# exp20.net
KiCad netlist of a schematic drawn in EAGLE
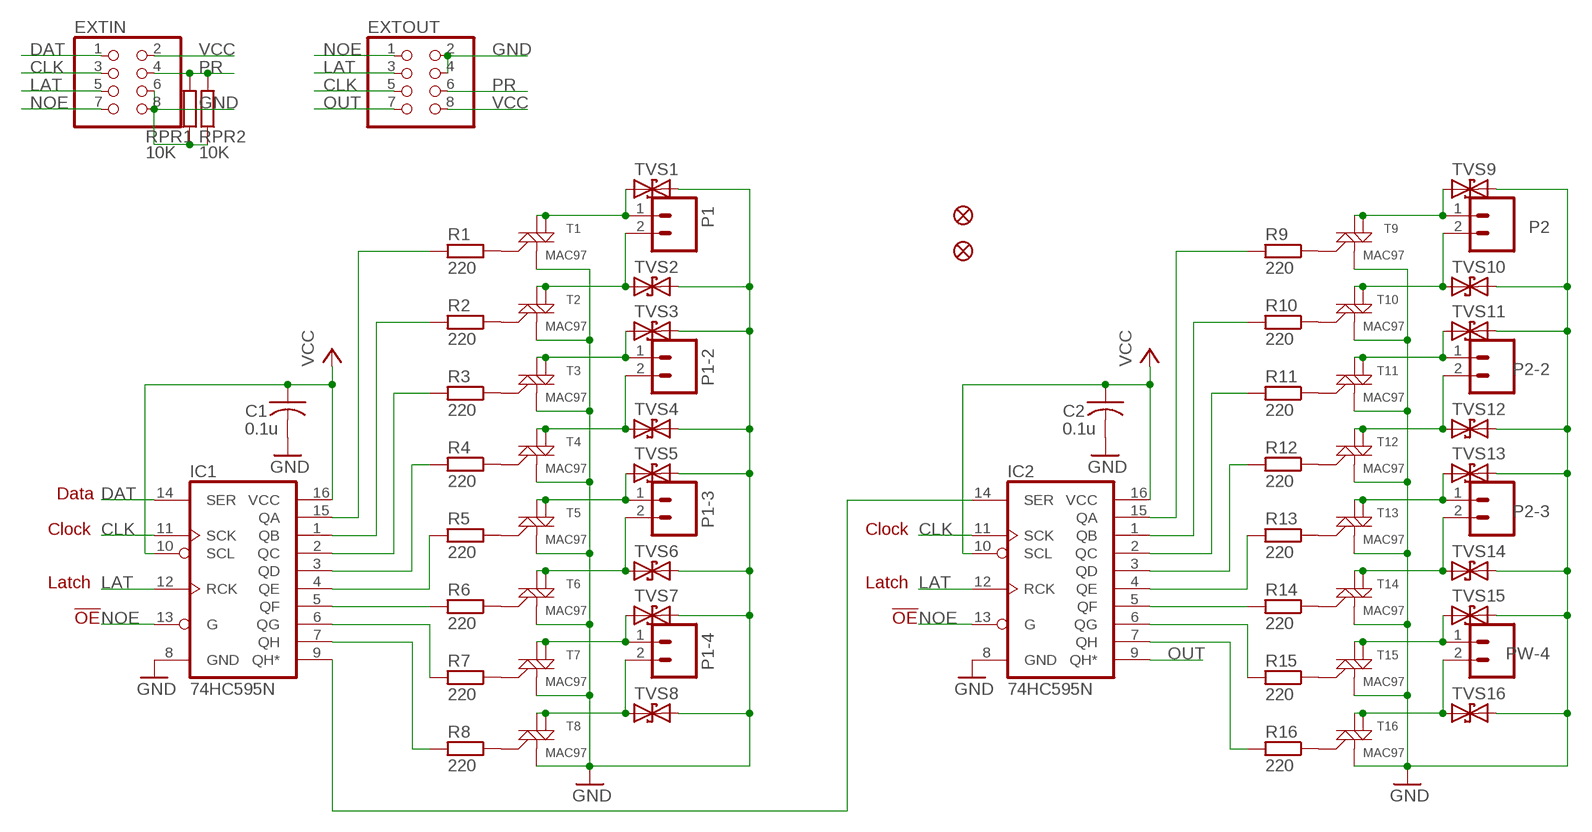
[diagram p0: schematic, sheet 1]

(export (version "E")
  (design (tool "Eeschema 10.0.6"))
  (components
    (comp (ref "C1")
      (value "0.1u")
      (footprint "eagle-import:C0805K")
      (libsource (lib "eagle-import") (part "C-USC0805K"))
    )
    (comp (ref "C2")
      (value "0.1u")
      (footprint "eagle-import:C0805K")
      (libsource (lib "eagle-import") (part "C-USC0805K"))
    )
    (comp (ref "EXTIN")
      (value "PINHD-2X4/90")
      (footprint "eagle-import:2X04_90")
      (libsource (lib "eagle-import") (part "PINHD-2X4/90"))
    )
    (comp (ref "EXTOUT")
      (value "PINHD-2X4/90")
      (footprint "eagle-import:2X04_90")
      (libsource (lib "eagle-import") (part "PINHD-2X4/90"))
    )
    (comp (ref "IC1")
      (value "74HC595N")
      (footprint "eagle-import:SO16")
      (libsource (lib "eagle-import") (part "74595DLS"))
    )
    (comp (ref "IC2")
      (value "74HC595N")
      (footprint "eagle-import:SO16")
      (libsource (lib "eagle-import") (part "74595DLS"))
    )
    (comp (ref "JP1")
      (value "FIDUCIAL1X2")
      (footprint "eagle-import:FIDUCIAL-1X2")
      (libsource (lib "eagle-import") (part "FIDUCIAL1X2"))
    )
    (comp (ref "JP2")
      (value "FIDUCIAL1X2")
      (footprint "eagle-import:FIDUCIAL-1X2")
      (libsource (lib "eagle-import") (part "FIDUCIAL1X2"))
    )
    (comp (ref "P1")
      (value "M025MM-X")
      (footprint "eagle-import:SCREWTERMINAL-5MM-2-X")
      (libsource (lib "eagle-import") (part "M025MM-X"))
    )
    (comp (ref "P1-2")
      (value "M025MM-X")
      (footprint "eagle-import:SCREWTERMINAL-5MM-2-X")
      (libsource (lib "eagle-import") (part "M025MM-X"))
    )
    (comp (ref "P1-3")
      (value "M025MM-X")
      (footprint "eagle-import:SCREWTERMINAL-5MM-2-X")
      (libsource (lib "eagle-import") (part "M025MM-X"))
    )
    (comp (ref "P1-4")
      (value "M025MM-X")
      (footprint "eagle-import:SCREWTERMINAL-5MM-2-X")
      (libsource (lib "eagle-import") (part "M025MM-X"))
    )
    (comp (ref "P2")
      (value "M025MM-X")
      (footprint "eagle-import:SCREWTERMINAL-5MM-2-X")
      (libsource (lib "eagle-import") (part "M025MM-X"))
    )
    (comp (ref "P2-2")
      (value "M025MM-X")
      (footprint "eagle-import:SCREWTERMINAL-5MM-2-X")
      (libsource (lib "eagle-import") (part "M025MM-X"))
    )
    (comp (ref "P2-3")
      (value "M025MM-X")
      (footprint "eagle-import:SCREWTERMINAL-5MM-2-X")
      (libsource (lib "eagle-import") (part "M025MM-X"))
    )
    (comp (ref "PW-4")
      (value "M025MM-X")
      (footprint "eagle-import:SCREWTERMINAL-5MM-2-X")
      (libsource (lib "eagle-import") (part "M025MM-X"))
    )
    (comp (ref "R1")
      (value "220")
      (footprint "eagle-import:R0805")
      (libsource (lib "eagle-import") (part "R-EU_R0805"))
    )
    (comp (ref "R2")
      (value "220")
      (footprint "eagle-import:R0805")
      (libsource (lib "eagle-import") (part "R-EU_R0805"))
    )
    (comp (ref "R3")
      (value "220")
      (footprint "eagle-import:R0805")
      (libsource (lib "eagle-import") (part "R-EU_R0805"))
    )
    (comp (ref "R4")
      (value "220")
      (footprint "eagle-import:R0805")
      (libsource (lib "eagle-import") (part "R-EU_R0805"))
    )
    (comp (ref "R5")
      (value "220")
      (footprint "eagle-import:R0805")
      (libsource (lib "eagle-import") (part "R-EU_R0805"))
    )
    (comp (ref "R6")
      (value "220")
      (footprint "eagle-import:R0805")
      (libsource (lib "eagle-import") (part "R-EU_R0805"))
    )
    (comp (ref "R7")
      (value "220")
      (footprint "eagle-import:R0805")
      (libsource (lib "eagle-import") (part "R-EU_R0805"))
    )
    (comp (ref "R8")
      (value "220")
      (footprint "eagle-import:R0805")
      (libsource (lib "eagle-import") (part "R-EU_R0805"))
    )
    (comp (ref "R9")
      (value "220")
      (footprint "eagle-import:R0805")
      (libsource (lib "eagle-import") (part "R-EU_R0805"))
    )
    (comp (ref "R10")
      (value "220")
      (footprint "eagle-import:R0805")
      (libsource (lib "eagle-import") (part "R-EU_R0805"))
    )
    (comp (ref "R11")
      (value "220")
      (footprint "eagle-import:R0805")
      (libsource (lib "eagle-import") (part "R-EU_R0805"))
    )
    (comp (ref "R12")
      (value "220")
      (footprint "eagle-import:R0805")
      (libsource (lib "eagle-import") (part "R-EU_R0805"))
    )
    (comp (ref "R13")
      (value "220")
      (footprint "eagle-import:R0805")
      (libsource (lib "eagle-import") (part "R-EU_R0805"))
    )
    (comp (ref "R14")
      (value "220")
      (footprint "eagle-import:R0805")
      (libsource (lib "eagle-import") (part "R-EU_R0805"))
    )
    (comp (ref "R15")
      (value "220")
      (footprint "eagle-import:R0805")
      (libsource (lib "eagle-import") (part "R-EU_R0805"))
    )
    (comp (ref "R16")
      (value "220")
      (footprint "eagle-import:R0805")
      (libsource (lib "eagle-import") (part "R-EU_R0805"))
    )
    (comp (ref "RPR1")
      (value "10K")
      (footprint "eagle-import:R0805")
      (libsource (lib "eagle-import") (part "R-EU_R0805"))
    )
    (comp (ref "RPR2")
      (value "10K")
      (footprint "eagle-import:R0805")
      (libsource (lib "eagle-import") (part "R-EU_R0805"))
    )
    (comp (ref "T1")
      (value "MAC97")
      (footprint "eagle-import:SOT223")
      (libsource (lib "eagle-import") (part "MAC97SOT223"))
    )
    (comp (ref "T2")
      (value "MAC97")
      (footprint "eagle-import:SOT223")
      (libsource (lib "eagle-import") (part "MAC97SOT223"))
    )
    (comp (ref "T3")
      (value "MAC97")
      (footprint "eagle-import:SOT223")
      (libsource (lib "eagle-import") (part "MAC97SOT223"))
    )
    (comp (ref "T4")
      (value "MAC97")
      (footprint "eagle-import:SOT223")
      (libsource (lib "eagle-import") (part "MAC97SOT223"))
    )
    (comp (ref "T5")
      (value "MAC97")
      (footprint "eagle-import:SOT223")
      (libsource (lib "eagle-import") (part "MAC97SOT223"))
    )
    (comp (ref "T6")
      (value "MAC97")
      (footprint "eagle-import:SOT223")
      (libsource (lib "eagle-import") (part "MAC97SOT223"))
    )
    (comp (ref "T7")
      (value "MAC97")
      (footprint "eagle-import:SOT223")
      (libsource (lib "eagle-import") (part "MAC97SOT223"))
    )
    (comp (ref "T8")
      (value "MAC97")
      (footprint "eagle-import:SOT223")
      (libsource (lib "eagle-import") (part "MAC97SOT223"))
    )
    (comp (ref "T9")
      (value "MAC97")
      (footprint "eagle-import:SOT223")
      (libsource (lib "eagle-import") (part "MAC97SOT223"))
    )
    (comp (ref "T10")
      (value "MAC97")
      (footprint "eagle-import:SOT223")
      (libsource (lib "eagle-import") (part "MAC97SOT223"))
    )
    (comp (ref "T11")
      (value "MAC97")
      (footprint "eagle-import:SOT223")
      (libsource (lib "eagle-import") (part "MAC97SOT223"))
    )
    (comp (ref "T12")
      (value "MAC97")
      (footprint "eagle-import:SOT223")
      (libsource (lib "eagle-import") (part "MAC97SOT223"))
    )
    (comp (ref "T13")
      (value "MAC97")
      (footprint "eagle-import:SOT223")
      (libsource (lib "eagle-import") (part "MAC97SOT223"))
    )
    (comp (ref "T14")
      (value "MAC97")
      (footprint "eagle-import:SOT223")
      (libsource (lib "eagle-import") (part "MAC97SOT223"))
    )
    (comp (ref "T15")
      (value "MAC97")
      (footprint "eagle-import:SOT223")
      (libsource (lib "eagle-import") (part "MAC97SOT223"))
    )
    (comp (ref "T16")
      (value "MAC97")
      (footprint "eagle-import:SOT223")
      (libsource (lib "eagle-import") (part "MAC97SOT223"))
    )
    (comp (ref "TVS1")
      (value "TVSSMB")
      (footprint "eagle-import:SMB")
      (libsource (lib "eagle-import") (part "TVSSMB"))
    )
    (comp (ref "TVS2")
      (value "TVSSMB")
      (footprint "eagle-import:SMB")
      (libsource (lib "eagle-import") (part "TVSSMB"))
    )
    (comp (ref "TVS3")
      (value "TVSSMB")
      (footprint "eagle-import:SMB")
      (libsource (lib "eagle-import") (part "TVSSMB"))
    )
    (comp (ref "TVS4")
      (value "TVSSMB")
      (footprint "eagle-import:SMB")
      (libsource (lib "eagle-import") (part "TVSSMB"))
    )
    (comp (ref "TVS5")
      (value "TVSSMB")
      (footprint "eagle-import:SMB")
      (libsource (lib "eagle-import") (part "TVSSMB"))
    )
    (comp (ref "TVS6")
      (value "TVSSMB")
      (footprint "eagle-import:SMB")
      (libsource (lib "eagle-import") (part "TVSSMB"))
    )
    (comp (ref "TVS7")
      (value "TVSSMB")
      (footprint "eagle-import:SMB")
      (libsource (lib "eagle-import") (part "TVSSMB"))
    )
    (comp (ref "TVS8")
      (value "TVSSMB")
      (footprint "eagle-import:SMB")
      (libsource (lib "eagle-import") (part "TVSSMB"))
    )
    (comp (ref "TVS9")
      (value "TVSSMB")
      (footprint "eagle-import:SMB")
      (libsource (lib "eagle-import") (part "TVSSMB"))
    )
    (comp (ref "TVS10")
      (value "TVSSMB")
      (footprint "eagle-import:SMB")
      (libsource (lib "eagle-import") (part "TVSSMB"))
    )
    (comp (ref "TVS11")
      (value "TVSSMB")
      (footprint "eagle-import:SMB")
      (libsource (lib "eagle-import") (part "TVSSMB"))
    )
    (comp (ref "TVS12")
      (value "TVSSMB")
      (footprint "eagle-import:SMB")
      (libsource (lib "eagle-import") (part "TVSSMB"))
    )
    (comp (ref "TVS13")
      (value "TVSSMB")
      (footprint "eagle-import:SMB")
      (libsource (lib "eagle-import") (part "TVSSMB"))
    )
    (comp (ref "TVS14")
      (value "TVSSMB")
      (footprint "eagle-import:SMB")
      (libsource (lib "eagle-import") (part "TVSSMB"))
    )
    (comp (ref "TVS15")
      (value "TVSSMB")
      (footprint "eagle-import:SMB")
      (libsource (lib "eagle-import") (part "TVSSMB"))
    )
    (comp (ref "TVS16")
      (value "TVSSMB")
      (footprint "eagle-import:SMB")
      (libsource (lib "eagle-import") (part "TVSSMB"))
    )
  )
  (nets
    (net (code "1") (name "/CLK") (class "Default")
      (node (ref "EXTIN") (pin "3") (pinfunction "3_3") (pintype "passive"))
      (node (ref "EXTOUT") (pin "5") (pinfunction "5_5") (pintype "passive"))
      (node (ref "IC1") (pin "11") (pinfunction "SCK_11") (pintype "input"))
      (node (ref "IC2") (pin "11") (pinfunction "SCK_11") (pintype "input"))
    )
    (net (code "2") (name "/DAT") (class "Default")
      (node (ref "EXTIN") (pin "1") (pinfunction "1_1") (pintype "passive"))
      (node (ref "IC1") (pin "14") (pinfunction "SER_14") (pintype "input"))
    )
    (net (code "3") (name "/LAT") (class "Default")
      (node (ref "EXTIN") (pin "5") (pinfunction "5_5") (pintype "passive"))
      (node (ref "EXTOUT") (pin "3") (pinfunction "3_3") (pintype "passive"))
      (node (ref "IC1") (pin "12") (pinfunction "RCK_12") (pintype "input"))
      (node (ref "IC2") (pin "12") (pinfunction "RCK_12") (pintype "input"))
    )
    (net (code "4") (name "/NOE") (class "Default")
      (node (ref "EXTIN") (pin "7") (pinfunction "7_7") (pintype "passive"))
      (node (ref "EXTOUT") (pin "1") (pinfunction "1_1") (pintype "passive"))
      (node (ref "IC1") (pin "13") (pinfunction "G_13") (pintype "input"))
      (node (ref "IC2") (pin "13") (pinfunction "G_13") (pintype "input"))
    )
    (net (code "5") (name "/OUT") (class "Default")
      (node (ref "EXTOUT") (pin "7") (pinfunction "7_7") (pintype "passive"))
      (node (ref "IC2") (pin "9") (pinfunction "QH*_9") (pintype "tri_state"))
    )
    (net (code "6") (name "/PR") (class "Default")
      (node (ref "EXTIN") (pin "4") (pinfunction "4_4") (pintype "passive"))
      (node (ref "EXTOUT") (pin "6") (pinfunction "6_6") (pintype "passive"))
      (node (ref "RPR1") (pin "2") (pinfunction "2_2") (pintype "passive"))
      (node (ref "RPR2") (pin "2") (pinfunction "2_2") (pintype "passive"))
    )
    (net (code "7") (name "GND") (class "Default")
      (node (ref "C1") (pin "2") (pinfunction "2_2") (pintype "passive"))
      (node (ref "C2") (pin "2") (pinfunction "2_2") (pintype "passive"))
      (node (ref "EXTIN") (pin "6") (pinfunction "6_6") (pintype "passive"))
      (node (ref "EXTIN") (pin "8") (pinfunction "8_8") (pintype "passive"))
      (node (ref "EXTOUT") (pin "2") (pinfunction "2_2") (pintype "passive"))
      (node (ref "EXTOUT") (pin "4") (pinfunction "4_4") (pintype "passive"))
      (node (ref "IC1") (pin "8") (pinfunction "GND_8") (pintype "power_in"))
      (node (ref "IC2") (pin "8") (pinfunction "GND_8") (pintype "power_in"))
      (node (ref "RPR1") (pin "1") (pinfunction "1_1") (pintype "passive"))
      (node (ref "RPR2") (pin "1") (pinfunction "1_1") (pintype "passive"))
      (node (ref "T1") (pin "1") (pinfunction "M1_1") (pintype "bidirectional"))
      (node (ref "T10") (pin "1") (pinfunction "M1_1") (pintype "bidirectional"))
      (node (ref "T11") (pin "1") (pinfunction "M1_1") (pintype "bidirectional"))
      (node (ref "T12") (pin "1") (pinfunction "M1_1") (pintype "bidirectional"))
      (node (ref "T13") (pin "1") (pinfunction "M1_1") (pintype "bidirectional"))
      (node (ref "T14") (pin "1") (pinfunction "M1_1") (pintype "bidirectional"))
      (node (ref "T15") (pin "1") (pinfunction "M1_1") (pintype "bidirectional"))
      (node (ref "T16") (pin "1") (pinfunction "M1_1") (pintype "bidirectional"))
      (node (ref "T2") (pin "1") (pinfunction "M1_1") (pintype "bidirectional"))
      (node (ref "T3") (pin "1") (pinfunction "M1_1") (pintype "bidirectional"))
      (node (ref "T4") (pin "1") (pinfunction "M1_1") (pintype "bidirectional"))
      (node (ref "T5") (pin "1") (pinfunction "M1_1") (pintype "bidirectional"))
      (node (ref "T6") (pin "1") (pinfunction "M1_1") (pintype "bidirectional"))
      (node (ref "T7") (pin "1") (pinfunction "M1_1") (pintype "bidirectional"))
      (node (ref "T8") (pin "1") (pinfunction "M1_1") (pintype "bidirectional"))
      (node (ref "T9") (pin "1") (pinfunction "M1_1") (pintype "bidirectional"))
      (node (ref "TVS1") (pin "C") (pinfunction "2_C") (pintype "passive"))
      (node (ref "TVS10") (pin "C") (pinfunction "2_C") (pintype "passive"))
      (node (ref "TVS11") (pin "C") (pinfunction "2_C") (pintype "passive"))
      (node (ref "TVS12") (pin "C") (pinfunction "2_C") (pintype "passive"))
      (node (ref "TVS13") (pin "C") (pinfunction "2_C") (pintype "passive"))
      (node (ref "TVS14") (pin "C") (pinfunction "2_C") (pintype "passive"))
      (node (ref "TVS15") (pin "C") (pinfunction "2_C") (pintype "passive"))
      (node (ref "TVS16") (pin "C") (pinfunction "2_C") (pintype "passive"))
      (node (ref "TVS2") (pin "C") (pinfunction "2_C") (pintype "passive"))
      (node (ref "TVS3") (pin "C") (pinfunction "2_C") (pintype "passive"))
      (node (ref "TVS4") (pin "C") (pinfunction "2_C") (pintype "passive"))
      (node (ref "TVS5") (pin "C") (pinfunction "2_C") (pintype "passive"))
      (node (ref "TVS6") (pin "C") (pinfunction "2_C") (pintype "passive"))
      (node (ref "TVS7") (pin "C") (pinfunction "2_C") (pintype "passive"))
      (node (ref "TVS8") (pin "C") (pinfunction "2_C") (pintype "passive"))
      (node (ref "TVS9") (pin "C") (pinfunction "2_C") (pintype "passive"))
    )
    (net (code "8") (name "Net-(IC1-QA)") (class "Default")
      (node (ref "IC1") (pin "15") (pinfunction "QA_15") (pintype "tri_state"))
      (node (ref "R1") (pin "2") (pinfunction "2_2") (pintype "passive"))
    )
    (net (code "9") (name "Net-(IC1-QB)") (class "Default")
      (node (ref "IC1") (pin "1") (pinfunction "QB_1") (pintype "tri_state"))
      (node (ref "R2") (pin "2") (pinfunction "2_2") (pintype "passive"))
    )
    (net (code "10") (name "Net-(IC1-QC)") (class "Default")
      (node (ref "IC1") (pin "2") (pinfunction "QC_2") (pintype "tri_state"))
      (node (ref "R3") (pin "2") (pinfunction "2_2") (pintype "passive"))
    )
    (net (code "11") (name "Net-(IC1-QD)") (class "Default")
      (node (ref "IC1") (pin "3") (pinfunction "QD_3") (pintype "tri_state"))
      (node (ref "R4") (pin "2") (pinfunction "2_2") (pintype "passive"))
    )
    (net (code "12") (name "Net-(IC1-QE)") (class "Default")
      (node (ref "IC1") (pin "4") (pinfunction "QE_4") (pintype "tri_state"))
      (node (ref "R5") (pin "2") (pinfunction "2_2") (pintype "passive"))
    )
    (net (code "13") (name "Net-(IC1-QF)") (class "Default")
      (node (ref "IC1") (pin "5") (pinfunction "QF_5") (pintype "tri_state"))
      (node (ref "R6") (pin "2") (pinfunction "2_2") (pintype "passive"))
    )
    (net (code "14") (name "Net-(IC1-QG)") (class "Default")
      (node (ref "IC1") (pin "6") (pinfunction "QG_6") (pintype "tri_state"))
      (node (ref "R7") (pin "2") (pinfunction "2_2") (pintype "passive"))
    )
    (net (code "15") (name "Net-(IC1-QH)") (class "Default")
      (node (ref "IC1") (pin "7") (pinfunction "QH_7") (pintype "tri_state"))
      (node (ref "R8") (pin "2") (pinfunction "2_2") (pintype "passive"))
    )
    (net (code "16") (name "Net-(IC1-QH*)") (class "Default")
      (node (ref "IC1") (pin "9") (pinfunction "QH*_9") (pintype "tri_state"))
      (node (ref "IC2") (pin "14") (pinfunction "SER_14") (pintype "input"))
    )
    (net (code "17") (name "Net-(IC2-QA)") (class "Default")
      (node (ref "IC2") (pin "15") (pinfunction "QA_15") (pintype "tri_state"))
      (node (ref "R9") (pin "2") (pinfunction "2_2") (pintype "passive"))
    )
    (net (code "18") (name "Net-(IC2-QB)") (class "Default")
      (node (ref "IC2") (pin "1") (pinfunction "QB_1") (pintype "tri_state"))
      (node (ref "R10") (pin "2") (pinfunction "2_2") (pintype "passive"))
    )
    (net (code "19") (name "Net-(IC2-QC)") (class "Default")
      (node (ref "IC2") (pin "2") (pinfunction "QC_2") (pintype "tri_state"))
      (node (ref "R11") (pin "2") (pinfunction "2_2") (pintype "passive"))
    )
    (net (code "20") (name "Net-(IC2-QD)") (class "Default")
      (node (ref "IC2") (pin "3") (pinfunction "QD_3") (pintype "tri_state"))
      (node (ref "R12") (pin "2") (pinfunction "2_2") (pintype "passive"))
    )
    (net (code "21") (name "Net-(IC2-QE)") (class "Default")
      (node (ref "IC2") (pin "4") (pinfunction "QE_4") (pintype "tri_state"))
      (node (ref "R13") (pin "2") (pinfunction "2_2") (pintype "passive"))
    )
    (net (code "22") (name "Net-(IC2-QF)") (class "Default")
      (node (ref "IC2") (pin "5") (pinfunction "QF_5") (pintype "tri_state"))
      (node (ref "R14") (pin "2") (pinfunction "2_2") (pintype "passive"))
    )
    (net (code "23") (name "Net-(IC2-QG)") (class "Default")
      (node (ref "IC2") (pin "6") (pinfunction "QG_6") (pintype "tri_state"))
      (node (ref "R15") (pin "2") (pinfunction "2_2") (pintype "passive"))
    )
    (net (code "24") (name "Net-(IC2-QH)") (class "Default")
      (node (ref "IC2") (pin "7") (pinfunction "QH_7") (pintype "tri_state"))
      (node (ref "R16") (pin "2") (pinfunction "2_2") (pintype "passive"))
    )
    (net (code "25") (name "Net-(T1-G)") (class "Default")
      (node (ref "R1") (pin "1") (pinfunction "1_1") (pintype "passive"))
      (node (ref "T1") (pin "3") (pinfunction "G_3") (pintype "bidirectional"))
    )
    (net (code "26") (name "Net-(T1-M2)") (class "Default")
      (node (ref "P1") (pin "1") (pinfunction "1_1") (pintype "passive"))
      (node (ref "T1") (pin "2") (pinfunction "M2_2") (pintype "bidirectional"))
      (node (ref "T1") (pin "4") (pinfunction "M2-4_4") (pintype "bidirectional"))
      (node (ref "TVS1") (pin "A") (pinfunction "1_A") (pintype "passive"))
    )
    (net (code "27") (name "Net-(T2-G)") (class "Default")
      (node (ref "R2") (pin "1") (pinfunction "1_1") (pintype "passive"))
      (node (ref "T2") (pin "3") (pinfunction "G_3") (pintype "bidirectional"))
    )
    (net (code "28") (name "Net-(T2-M2)") (class "Default")
      (node (ref "P1") (pin "2") (pinfunction "2_2") (pintype "passive"))
      (node (ref "T2") (pin "2") (pinfunction "M2_2") (pintype "bidirectional"))
      (node (ref "T2") (pin "4") (pinfunction "M2-4_4") (pintype "bidirectional"))
      (node (ref "TVS2") (pin "A") (pinfunction "1_A") (pintype "passive"))
    )
    (net (code "29") (name "Net-(T3-G)") (class "Default")
      (node (ref "R3") (pin "1") (pinfunction "1_1") (pintype "passive"))
      (node (ref "T3") (pin "3") (pinfunction "G_3") (pintype "bidirectional"))
    )
    (net (code "30") (name "Net-(T3-M2)") (class "Default")
      (node (ref "P1-2") (pin "1") (pinfunction "1_1") (pintype "passive"))
      (node (ref "T3") (pin "2") (pinfunction "M2_2") (pintype "bidirectional"))
      (node (ref "T3") (pin "4") (pinfunction "M2-4_4") (pintype "bidirectional"))
      (node (ref "TVS3") (pin "A") (pinfunction "1_A") (pintype "passive"))
    )
    (net (code "31") (name "Net-(T4-G)") (class "Default")
      (node (ref "R4") (pin "1") (pinfunction "1_1") (pintype "passive"))
      (node (ref "T4") (pin "3") (pinfunction "G_3") (pintype "bidirectional"))
    )
    (net (code "32") (name "Net-(T4-M2)") (class "Default")
      (node (ref "P1-2") (pin "2") (pinfunction "2_2") (pintype "passive"))
      (node (ref "T4") (pin "2") (pinfunction "M2_2") (pintype "bidirectional"))
      (node (ref "T4") (pin "4") (pinfunction "M2-4_4") (pintype "bidirectional"))
      (node (ref "TVS4") (pin "A") (pinfunction "1_A") (pintype "passive"))
    )
    (net (code "33") (name "Net-(T5-G)") (class "Default")
      (node (ref "R5") (pin "1") (pinfunction "1_1") (pintype "passive"))
      (node (ref "T5") (pin "3") (pinfunction "G_3") (pintype "bidirectional"))
    )
    (net (code "34") (name "Net-(T5-M2)") (class "Default")
      (node (ref "P1-3") (pin "1") (pinfunction "1_1") (pintype "passive"))
      (node (ref "T5") (pin "2") (pinfunction "M2_2") (pintype "bidirectional"))
      (node (ref "T5") (pin "4") (pinfunction "M2-4_4") (pintype "bidirectional"))
      (node (ref "TVS5") (pin "A") (pinfunction "1_A") (pintype "passive"))
    )
    (net (code "35") (name "Net-(T6-G)") (class "Default")
      (node (ref "R6") (pin "1") (pinfunction "1_1") (pintype "passive"))
      (node (ref "T6") (pin "3") (pinfunction "G_3") (pintype "bidirectional"))
    )
    (net (code "36") (name "Net-(T6-M2)") (class "Default")
      (node (ref "P1-3") (pin "2") (pinfunction "2_2") (pintype "passive"))
      (node (ref "T6") (pin "2") (pinfunction "M2_2") (pintype "bidirectional"))
      (node (ref "T6") (pin "4") (pinfunction "M2-4_4") (pintype "bidirectional"))
      (node (ref "TVS6") (pin "A") (pinfunction "1_A") (pintype "passive"))
    )
    (net (code "37") (name "Net-(T7-G)") (class "Default")
      (node (ref "R7") (pin "1") (pinfunction "1_1") (pintype "passive"))
      (node (ref "T7") (pin "3") (pinfunction "G_3") (pintype "bidirectional"))
    )
    (net (code "38") (name "Net-(T7-M2)") (class "Default")
      (node (ref "P1-4") (pin "1") (pinfunction "1_1") (pintype "passive"))
      (node (ref "T7") (pin "2") (pinfunction "M2_2") (pintype "bidirectional"))
      (node (ref "T7") (pin "4") (pinfunction "M2-4_4") (pintype "bidirectional"))
      (node (ref "TVS7") (pin "A") (pinfunction "1_A") (pintype "passive"))
    )
    (net (code "39") (name "Net-(T8-G)") (class "Default")
      (node (ref "R8") (pin "1") (pinfunction "1_1") (pintype "passive"))
      (node (ref "T8") (pin "3") (pinfunction "G_3") (pintype "bidirectional"))
    )
    (net (code "40") (name "Net-(T8-M2)") (class "Default")
      (node (ref "P1-4") (pin "2") (pinfunction "2_2") (pintype "passive"))
      (node (ref "T8") (pin "2") (pinfunction "M2_2") (pintype "bidirectional"))
      (node (ref "T8") (pin "4") (pinfunction "M2-4_4") (pintype "bidirectional"))
      (node (ref "TVS8") (pin "A") (pinfunction "1_A") (pintype "passive"))
    )
    (net (code "41") (name "Net-(T9-G)") (class "Default")
      (node (ref "R9") (pin "1") (pinfunction "1_1") (pintype "passive"))
      (node (ref "T9") (pin "3") (pinfunction "G_3") (pintype "bidirectional"))
    )
    (net (code "42") (name "Net-(T9-M2)") (class "Default")
      (node (ref "P2") (pin "1") (pinfunction "1_1") (pintype "passive"))
      (node (ref "T9") (pin "2") (pinfunction "M2_2") (pintype "bidirectional"))
      (node (ref "T9") (pin "4") (pinfunction "M2-4_4") (pintype "bidirectional"))
      (node (ref "TVS9") (pin "A") (pinfunction "1_A") (pintype "passive"))
    )
    (net (code "43") (name "Net-(T10-G)") (class "Default")
      (node (ref "R10") (pin "1") (pinfunction "1_1") (pintype "passive"))
      (node (ref "T10") (pin "3") (pinfunction "G_3") (pintype "bidirectional"))
    )
    (net (code "44") (name "Net-(T10-M2)") (class "Default")
      (node (ref "P2") (pin "2") (pinfunction "2_2") (pintype "passive"))
      (node (ref "T10") (pin "2") (pinfunction "M2_2") (pintype "bidirectional"))
      (node (ref "T10") (pin "4") (pinfunction "M2-4_4") (pintype "bidirectional"))
      (node (ref "TVS10") (pin "A") (pinfunction "1_A") (pintype "passive"))
    )
    (net (code "45") (name "Net-(T11-G)") (class "Default")
      (node (ref "R11") (pin "1") (pinfunction "1_1") (pintype "passive"))
      (node (ref "T11") (pin "3") (pinfunction "G_3") (pintype "bidirectional"))
    )
    (net (code "46") (name "Net-(T11-M2)") (class "Default")
      (node (ref "P2-2") (pin "1") (pinfunction "1_1") (pintype "passive"))
      (node (ref "T11") (pin "2") (pinfunction "M2_2") (pintype "bidirectional"))
      (node (ref "T11") (pin "4") (pinfunction "M2-4_4") (pintype "bidirectional"))
      (node (ref "TVS11") (pin "A") (pinfunction "1_A") (pintype "passive"))
    )
    (net (code "47") (name "Net-(T12-G)") (class "Default")
      (node (ref "R12") (pin "1") (pinfunction "1_1") (pintype "passive"))
      (node (ref "T12") (pin "3") (pinfunction "G_3") (pintype "bidirectional"))
    )
    (net (code "48") (name "Net-(T12-M2)") (class "Default")
      (node (ref "P2-2") (pin "2") (pinfunction "2_2") (pintype "passive"))
      (node (ref "T12") (pin "2") (pinfunction "M2_2") (pintype "bidirectional"))
      (node (ref "T12") (pin "4") (pinfunction "M2-4_4") (pintype "bidirectional"))
      (node (ref "TVS12") (pin "A") (pinfunction "1_A") (pintype "passive"))
    )
    (net (code "49") (name "Net-(T13-G)") (class "Default")
      (node (ref "R13") (pin "1") (pinfunction "1_1") (pintype "passive"))
      (node (ref "T13") (pin "3") (pinfunction "G_3") (pintype "bidirectional"))
    )
    (net (code "50") (name "Net-(T13-M2)") (class "Default")
      (node (ref "P2-3") (pin "1") (pinfunction "1_1") (pintype "passive"))
      (node (ref "T13") (pin "2") (pinfunction "M2_2") (pintype "bidirectional"))
      (node (ref "T13") (pin "4") (pinfunction "M2-4_4") (pintype "bidirectional"))
      (node (ref "TVS13") (pin "A") (pinfunction "1_A") (pintype "passive"))
    )
    (net (code "51") (name "Net-(T14-G)") (class "Default")
      (node (ref "R14") (pin "1") (pinfunction "1_1") (pintype "passive"))
      (node (ref "T14") (pin "3") (pinfunction "G_3") (pintype "bidirectional"))
    )
    (net (code "52") (name "Net-(T14-M2)") (class "Default")
      (node (ref "P2-3") (pin "2") (pinfunction "2_2") (pintype "passive"))
      (node (ref "T14") (pin "2") (pinfunction "M2_2") (pintype "bidirectional"))
      (node (ref "T14") (pin "4") (pinfunction "M2-4_4") (pintype "bidirectional"))
      (node (ref "TVS14") (pin "A") (pinfunction "1_A") (pintype "passive"))
    )
    (net (code "53") (name "Net-(T15-G)") (class "Default")
      (node (ref "R15") (pin "1") (pinfunction "1_1") (pintype "passive"))
      (node (ref "T15") (pin "3") (pinfunction "G_3") (pintype "bidirectional"))
    )
    (net (code "54") (name "Net-(T15-M2)") (class "Default")
      (node (ref "PW-4") (pin "1") (pinfunction "1_1") (pintype "passive"))
      (node (ref "T15") (pin "2") (pinfunction "M2_2") (pintype "bidirectional"))
      (node (ref "T15") (pin "4") (pinfunction "M2-4_4") (pintype "bidirectional"))
      (node (ref "TVS15") (pin "A") (pinfunction "1_A") (pintype "passive"))
    )
    (net (code "55") (name "Net-(T16-G)") (class "Default")
      (node (ref "R16") (pin "1") (pinfunction "1_1") (pintype "passive"))
      (node (ref "T16") (pin "3") (pinfunction "G_3") (pintype "bidirectional"))
    )
    (net (code "56") (name "Net-(T16-M2)") (class "Default")
      (node (ref "PW-4") (pin "2") (pinfunction "2_2") (pintype "passive"))
      (node (ref "T16") (pin "2") (pinfunction "M2_2") (pintype "bidirectional"))
      (node (ref "T16") (pin "4") (pinfunction "M2-4_4") (pintype "bidirectional"))
      (node (ref "TVS16") (pin "A") (pinfunction "1_A") (pintype "passive"))
    )
    (net (code "57") (name "VCC") (class "Default")
      (node (ref "C1") (pin "1") (pinfunction "1_1") (pintype "passive"))
      (node (ref "C2") (pin "1") (pinfunction "1_1") (pintype "passive"))
      (node (ref "EXTIN") (pin "2") (pinfunction "2_2") (pintype "passive"))
      (node (ref "EXTOUT") (pin "8") (pinfunction "8_8") (pintype "passive"))
      (node (ref "IC1") (pin "10") (pinfunction "SCL_10") (pintype "input"))
      (node (ref "IC1") (pin "16") (pinfunction "VCC_16") (pintype "power_in"))
      (node (ref "IC2") (pin "10") (pinfunction "SCL_10") (pintype "input"))
      (node (ref "IC2") (pin "16") (pinfunction "VCC_16") (pintype "power_in"))
    )
  )
)
